# schem.net
KiCad netlist of a schematic drawn in EAGLE
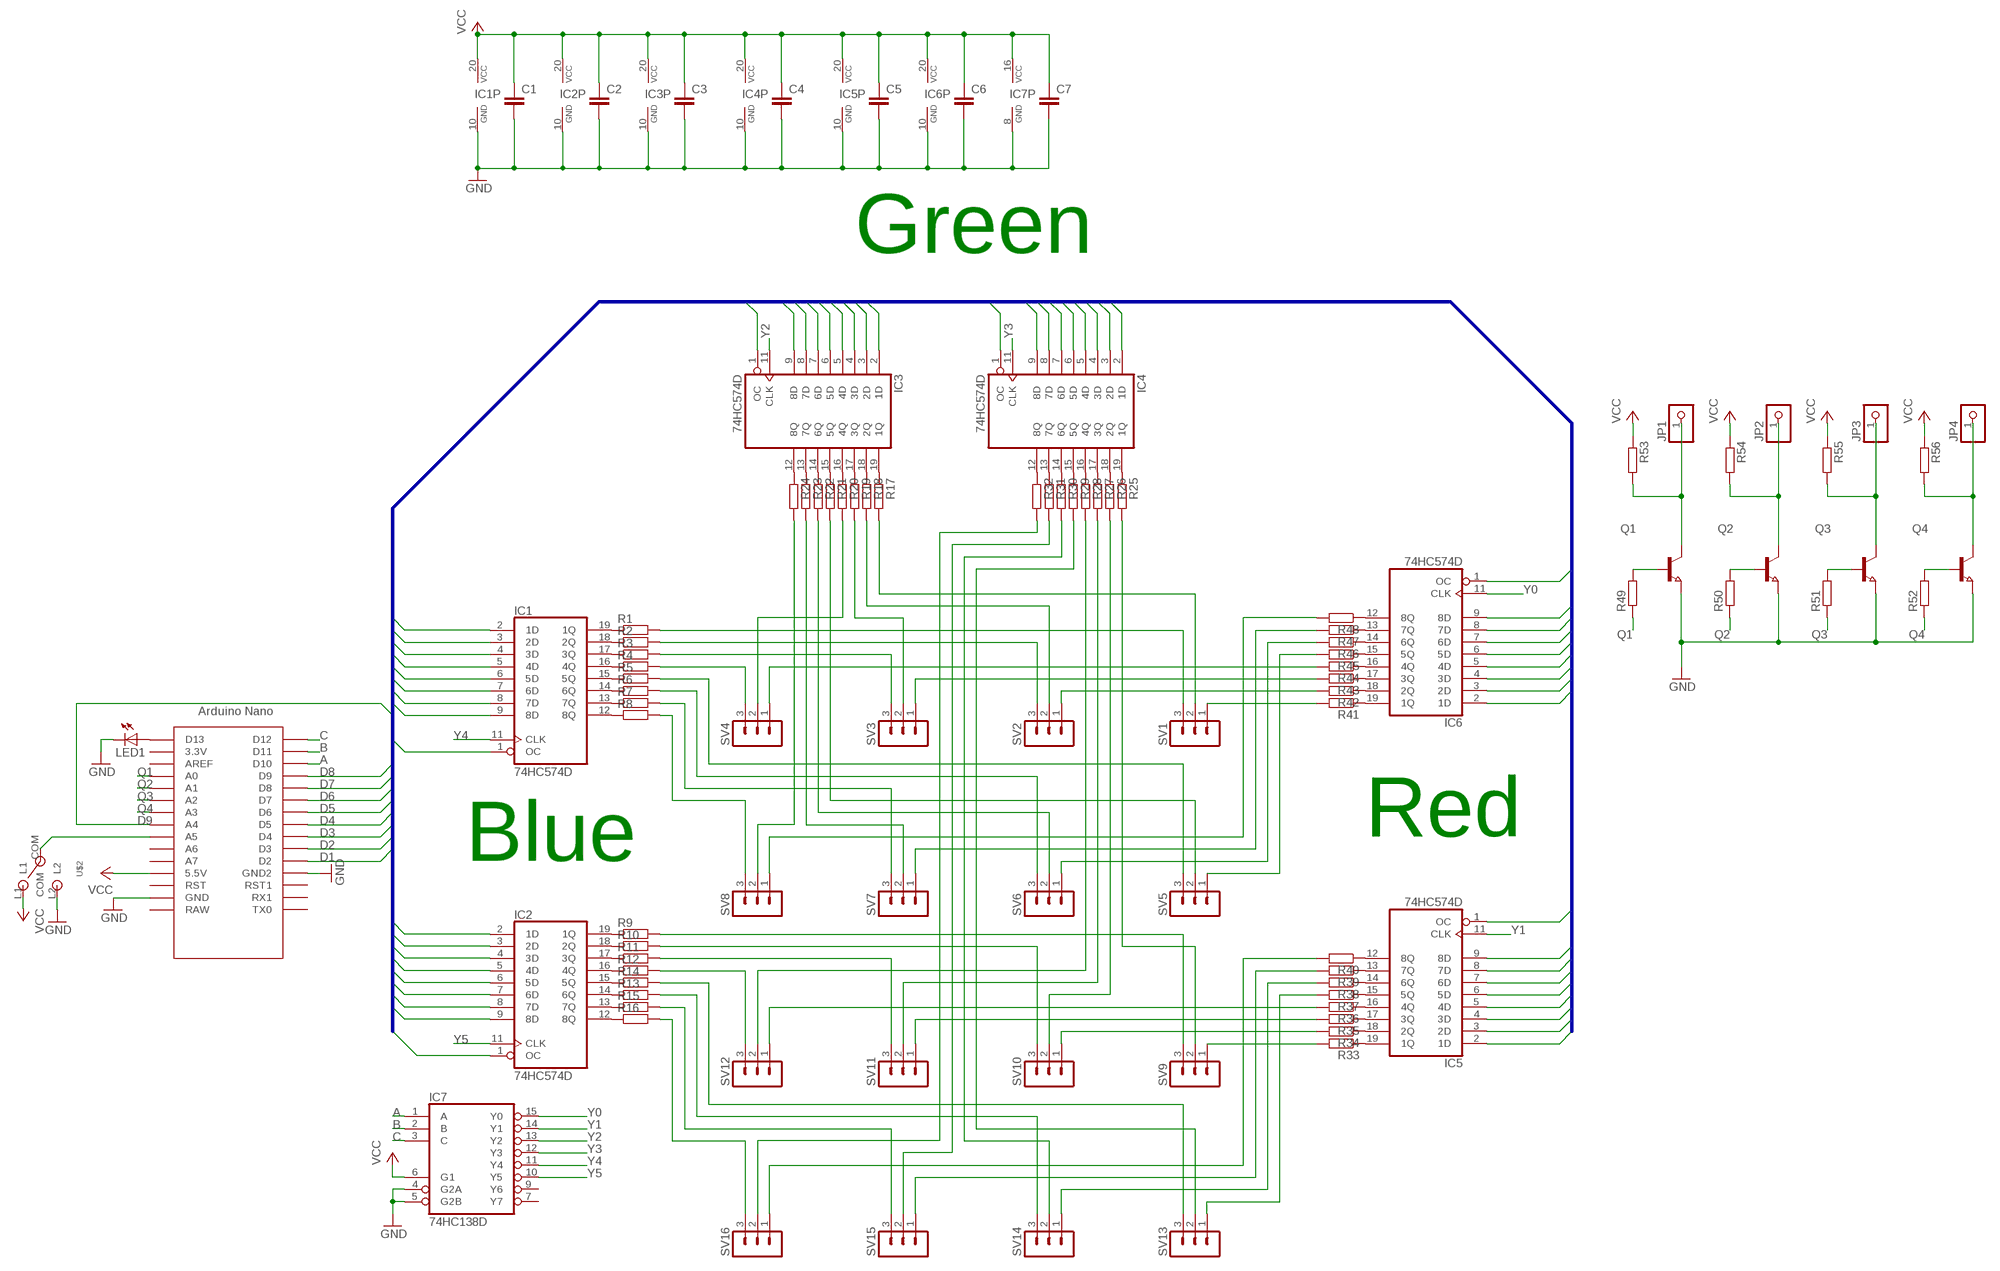
[diagram p0: schematic, sheet 1]

(export (version "E")
  (design (tool "Eeschema 10.0.6"))
  (components
    (comp (ref "C1")
      (value "C-EUC0805")
      (footprint "eagle-import:C0805")
      (libsource (lib "eagle-import") (part "C-EUC0805"))
    )
    (comp (ref "C2")
      (value "C-EUC0805")
      (footprint "eagle-import:C0805")
      (libsource (lib "eagle-import") (part "C-EUC0805"))
    )
    (comp (ref "C3")
      (value "C-EUC0805")
      (footprint "eagle-import:C0805")
      (libsource (lib "eagle-import") (part "C-EUC0805"))
    )
    (comp (ref "C4")
      (value "C-EUC0805")
      (footprint "eagle-import:C0805")
      (libsource (lib "eagle-import") (part "C-EUC0805"))
    )
    (comp (ref "C5")
      (value "C-EUC0805")
      (footprint "eagle-import:C0805")
      (libsource (lib "eagle-import") (part "C-EUC0805"))
    )
    (comp (ref "C6")
      (value "C-EUC0805")
      (footprint "eagle-import:C0805")
      (libsource (lib "eagle-import") (part "C-EUC0805"))
    )
    (comp (ref "C7")
      (value "C-EUC0805")
      (footprint "eagle-import:C0805")
      (libsource (lib "eagle-import") (part "C-EUC0805"))
    )
    (comp (ref "IC1")
      (value "74HC574D")
      (footprint "eagle-import:SO20W")
      (libsource (lib "eagle-import") (part "74574DHC"))
    )
    (comp (ref "IC2")
      (value "74HC574D")
      (footprint "eagle-import:SO20W")
      (libsource (lib "eagle-import") (part "74574DHC"))
    )
    (comp (ref "IC3")
      (value "74HC574D")
      (footprint "eagle-import:SO20W")
      (libsource (lib "eagle-import") (part "74574DHC"))
    )
    (comp (ref "IC4")
      (value "74HC574D")
      (footprint "eagle-import:SO20W")
      (libsource (lib "eagle-import") (part "74574DHC"))
    )
    (comp (ref "IC5")
      (value "74HC574D")
      (footprint "eagle-import:SO20W")
      (libsource (lib "eagle-import") (part "74574DHC"))
    )
    (comp (ref "IC6")
      (value "74HC574D")
      (footprint "eagle-import:SO20W")
      (libsource (lib "eagle-import") (part "74574DHC"))
    )
    (comp (ref "IC7")
      (value "74HC138D")
      (footprint "eagle-import:SO16")
      (libsource (lib "eagle-import") (part "74138DHC"))
    )
    (comp (ref "JP1")
      (value "PINHD-1X1")
      (footprint "eagle-import:1X01")
      (libsource (lib "eagle-import") (part "PINHD-1X1"))
    )
    (comp (ref "JP2")
      (value "PINHD-1X1")
      (footprint "eagle-import:1X01")
      (libsource (lib "eagle-import") (part "PINHD-1X1"))
    )
    (comp (ref "JP3")
      (value "PINHD-1X1")
      (footprint "eagle-import:1X01")
      (libsource (lib "eagle-import") (part "PINHD-1X1"))
    )
    (comp (ref "JP4")
      (value "PINHD-1X1")
      (footprint "eagle-import:1X01")
      (libsource (lib "eagle-import") (part "PINHD-1X1"))
    )
    (comp (ref "LED1")
      (value "LEDCHIP-LED0805")
      (footprint "eagle-import:CHIP-LED0805")
      (libsource (lib "eagle-import") (part "LEDCHIP-LED0805"))
    )
    (comp (ref "Q1")
      (value "NPN-TRANSISTOR_SOT23")
      (footprint "eagle-import:SOT23")
      (libsource (lib "eagle-import") (part "NPN-TRANSISTOR_SOT23"))
    )
    (comp (ref "Q2")
      (value "NPN-TRANSISTOR_SOT23")
      (footprint "eagle-import:SOT23")
      (libsource (lib "eagle-import") (part "NPN-TRANSISTOR_SOT23"))
    )
    (comp (ref "Q3")
      (value "NPN-TRANSISTOR_SOT23")
      (footprint "eagle-import:SOT23")
      (libsource (lib "eagle-import") (part "NPN-TRANSISTOR_SOT23"))
    )
    (comp (ref "Q4")
      (value "NPN-TRANSISTOR_SOT23")
      (footprint "eagle-import:SOT23")
      (libsource (lib "eagle-import") (part "NPN-TRANSISTOR_SOT23"))
    )
    (comp (ref "R1")
      (value "R-EU_R0805")
      (footprint "eagle-import:R0805")
      (libsource (lib "eagle-import") (part "R-EU_R0805"))
    )
    (comp (ref "R2")
      (value "R-EU_R0805")
      (footprint "eagle-import:R0805")
      (libsource (lib "eagle-import") (part "R-EU_R0805"))
    )
    (comp (ref "R3")
      (value "R-EU_R0805")
      (footprint "eagle-import:R0805")
      (libsource (lib "eagle-import") (part "R-EU_R0805"))
    )
    (comp (ref "R4")
      (value "R-EU_R0805")
      (footprint "eagle-import:R0805")
      (libsource (lib "eagle-import") (part "R-EU_R0805"))
    )
    (comp (ref "R5")
      (value "R-EU_R0805")
      (footprint "eagle-import:R0805")
      (libsource (lib "eagle-import") (part "R-EU_R0805"))
    )
    (comp (ref "R6")
      (value "R-EU_R0805")
      (footprint "eagle-import:R0805")
      (libsource (lib "eagle-import") (part "R-EU_R0805"))
    )
    (comp (ref "R7")
      (value "R-EU_R0805")
      (footprint "eagle-import:R0805")
      (libsource (lib "eagle-import") (part "R-EU_R0805"))
    )
    (comp (ref "R8")
      (value "R-EU_R0805")
      (footprint "eagle-import:R0805")
      (libsource (lib "eagle-import") (part "R-EU_R0805"))
    )
    (comp (ref "R9")
      (value "R-EU_R0805")
      (footprint "eagle-import:R0805")
      (libsource (lib "eagle-import") (part "R-EU_R0805"))
    )
    (comp (ref "R10")
      (value "R-EU_R0805")
      (footprint "eagle-import:R0805")
      (libsource (lib "eagle-import") (part "R-EU_R0805"))
    )
    (comp (ref "R11")
      (value "R-EU_R0805")
      (footprint "eagle-import:R0805")
      (libsource (lib "eagle-import") (part "R-EU_R0805"))
    )
    (comp (ref "R12")
      (value "R-EU_R0805")
      (footprint "eagle-import:R0805")
      (libsource (lib "eagle-import") (part "R-EU_R0805"))
    )
    (comp (ref "R13")
      (value "R-EU_R0805")
      (footprint "eagle-import:R0805")
      (libsource (lib "eagle-import") (part "R-EU_R0805"))
    )
    (comp (ref "R14")
      (value "R-EU_R0805")
      (footprint "eagle-import:R0805")
      (libsource (lib "eagle-import") (part "R-EU_R0805"))
    )
    (comp (ref "R15")
      (value "R-EU_R0805")
      (footprint "eagle-import:R0805")
      (libsource (lib "eagle-import") (part "R-EU_R0805"))
    )
    (comp (ref "R16")
      (value "R-EU_R0805")
      (footprint "eagle-import:R0805")
      (libsource (lib "eagle-import") (part "R-EU_R0805"))
    )
    (comp (ref "R17")
      (value "R-EU_R0805")
      (footprint "eagle-import:R0805")
      (libsource (lib "eagle-import") (part "R-EU_R0805"))
    )
    (comp (ref "R18")
      (value "R-EU_R0805")
      (footprint "eagle-import:R0805")
      (libsource (lib "eagle-import") (part "R-EU_R0805"))
    )
    (comp (ref "R19")
      (value "R-EU_R0805")
      (footprint "eagle-import:R0805")
      (libsource (lib "eagle-import") (part "R-EU_R0805"))
    )
    (comp (ref "R20")
      (value "R-EU_R0805")
      (footprint "eagle-import:R0805")
      (libsource (lib "eagle-import") (part "R-EU_R0805"))
    )
    (comp (ref "R21")
      (value "R-EU_R0805")
      (footprint "eagle-import:R0805")
      (libsource (lib "eagle-import") (part "R-EU_R0805"))
    )
    (comp (ref "R22")
      (value "R-EU_R0805")
      (footprint "eagle-import:R0805")
      (libsource (lib "eagle-import") (part "R-EU_R0805"))
    )
    (comp (ref "R23")
      (value "R-EU_R0805")
      (footprint "eagle-import:R0805")
      (libsource (lib "eagle-import") (part "R-EU_R0805"))
    )
    (comp (ref "R24")
      (value "R-EU_R0805")
      (footprint "eagle-import:R0805")
      (libsource (lib "eagle-import") (part "R-EU_R0805"))
    )
    (comp (ref "R25")
      (value "R-EU_R0805")
      (footprint "eagle-import:R0805")
      (libsource (lib "eagle-import") (part "R-EU_R0805"))
    )
    (comp (ref "R26")
      (value "R-EU_R0805")
      (footprint "eagle-import:R0805")
      (libsource (lib "eagle-import") (part "R-EU_R0805"))
    )
    (comp (ref "R27")
      (value "R-EU_R0805")
      (footprint "eagle-import:R0805")
      (libsource (lib "eagle-import") (part "R-EU_R0805"))
    )
    (comp (ref "R28")
      (value "R-EU_R0805")
      (footprint "eagle-import:R0805")
      (libsource (lib "eagle-import") (part "R-EU_R0805"))
    )
    (comp (ref "R29")
      (value "R-EU_R0805")
      (footprint "eagle-import:R0805")
      (libsource (lib "eagle-import") (part "R-EU_R0805"))
    )
    (comp (ref "R30")
      (value "R-EU_R0805")
      (footprint "eagle-import:R0805")
      (libsource (lib "eagle-import") (part "R-EU_R0805"))
    )
    (comp (ref "R31")
      (value "R-EU_R0805")
      (footprint "eagle-import:R0805")
      (libsource (lib "eagle-import") (part "R-EU_R0805"))
    )
    (comp (ref "R32")
      (value "R-EU_R0805")
      (footprint "eagle-import:R0805")
      (libsource (lib "eagle-import") (part "R-EU_R0805"))
    )
    (comp (ref "R33")
      (value "R-EU_R0805")
      (footprint "eagle-import:R0805")
      (libsource (lib "eagle-import") (part "R-EU_R0805"))
    )
    (comp (ref "R34")
      (value "R-EU_R0805")
      (footprint "eagle-import:R0805")
      (libsource (lib "eagle-import") (part "R-EU_R0805"))
    )
    (comp (ref "R35")
      (value "R-EU_R0805")
      (footprint "eagle-import:R0805")
      (libsource (lib "eagle-import") (part "R-EU_R0805"))
    )
    (comp (ref "R36")
      (value "R-EU_R0805")
      (footprint "eagle-import:R0805")
      (libsource (lib "eagle-import") (part "R-EU_R0805"))
    )
    (comp (ref "R37")
      (value "R-EU_R0805")
      (footprint "eagle-import:R0805")
      (libsource (lib "eagle-import") (part "R-EU_R0805"))
    )
    (comp (ref "R38")
      (value "R-EU_R0805")
      (footprint "eagle-import:R0805")
      (libsource (lib "eagle-import") (part "R-EU_R0805"))
    )
    (comp (ref "R39")
      (value "R-EU_R0805")
      (footprint "eagle-import:R0805")
      (libsource (lib "eagle-import") (part "R-EU_R0805"))
    )
    (comp (ref "R40")
      (value "R-EU_R0805")
      (footprint "eagle-import:R0805")
      (libsource (lib "eagle-import") (part "R-EU_R0805"))
    )
    (comp (ref "R41")
      (value "R-EU_R0805")
      (footprint "eagle-import:R0805")
      (libsource (lib "eagle-import") (part "R-EU_R0805"))
    )
    (comp (ref "R42")
      (value "R-EU_R0805")
      (footprint "eagle-import:R0805")
      (libsource (lib "eagle-import") (part "R-EU_R0805"))
    )
    (comp (ref "R43")
      (value "R-EU_R0805")
      (footprint "eagle-import:R0805")
      (libsource (lib "eagle-import") (part "R-EU_R0805"))
    )
    (comp (ref "R44")
      (value "R-EU_R0805")
      (footprint "eagle-import:R0805")
      (libsource (lib "eagle-import") (part "R-EU_R0805"))
    )
    (comp (ref "R45")
      (value "R-EU_R0805")
      (footprint "eagle-import:R0805")
      (libsource (lib "eagle-import") (part "R-EU_R0805"))
    )
    (comp (ref "R46")
      (value "R-EU_R0805")
      (footprint "eagle-import:R0805")
      (libsource (lib "eagle-import") (part "R-EU_R0805"))
    )
    (comp (ref "R47")
      (value "R-EU_R0805")
      (footprint "eagle-import:R0805")
      (libsource (lib "eagle-import") (part "R-EU_R0805"))
    )
    (comp (ref "R48")
      (value "R-EU_R0805")
      (footprint "eagle-import:R0805")
      (libsource (lib "eagle-import") (part "R-EU_R0805"))
    )
    (comp (ref "R49")
      (value "R-EU_R0805")
      (footprint "eagle-import:R0805")
      (libsource (lib "eagle-import") (part "R-EU_R0805"))
    )
    (comp (ref "R50")
      (value "R-EU_R0805")
      (footprint "eagle-import:R0805")
      (libsource (lib "eagle-import") (part "R-EU_R0805"))
    )
    (comp (ref "R51")
      (value "R-EU_R0805")
      (footprint "eagle-import:R0805")
      (libsource (lib "eagle-import") (part "R-EU_R0805"))
    )
    (comp (ref "R52")
      (value "R-EU_R0805")
      (footprint "eagle-import:R0805")
      (libsource (lib "eagle-import") (part "R-EU_R0805"))
    )
    (comp (ref "R53")
      (value "R-EU_R0805")
      (footprint "eagle-import:R0805")
      (libsource (lib "eagle-import") (part "R-EU_R0805"))
    )
    (comp (ref "R54")
      (value "R-EU_R0805")
      (footprint "eagle-import:R0805")
      (libsource (lib "eagle-import") (part "R-EU_R0805"))
    )
    (comp (ref "R55")
      (value "R-EU_R0805")
      (footprint "eagle-import:R0805")
      (libsource (lib "eagle-import") (part "R-EU_R0805"))
    )
    (comp (ref "R56")
      (value "R-EU_R0805")
      (footprint "eagle-import:R0805")
      (libsource (lib "eagle-import") (part "R-EU_R0805"))
    )
    (comp (ref "SV1")
      (value "MA03-1")
      (footprint "eagle-import:MA03-1")
      (libsource (lib "eagle-import") (part "MA03-1"))
    )
    (comp (ref "SV2")
      (value "MA03-1")
      (footprint "eagle-import:MA03-1")
      (libsource (lib "eagle-import") (part "MA03-1"))
    )
    (comp (ref "SV3")
      (value "MA03-1")
      (footprint "eagle-import:MA03-1")
      (libsource (lib "eagle-import") (part "MA03-1"))
    )
    (comp (ref "SV4")
      (value "MA03-1")
      (footprint "eagle-import:MA03-1")
      (libsource (lib "eagle-import") (part "MA03-1"))
    )
    (comp (ref "SV5")
      (value "MA03-1")
      (footprint "eagle-import:MA03-1")
      (libsource (lib "eagle-import") (part "MA03-1"))
    )
    (comp (ref "SV6")
      (value "MA03-1")
      (footprint "eagle-import:MA03-1")
      (libsource (lib "eagle-import") (part "MA03-1"))
    )
    (comp (ref "SV7")
      (value "MA03-1")
      (footprint "eagle-import:MA03-1")
      (libsource (lib "eagle-import") (part "MA03-1"))
    )
    (comp (ref "SV8")
      (value "MA03-1")
      (footprint "eagle-import:MA03-1")
      (libsource (lib "eagle-import") (part "MA03-1"))
    )
    (comp (ref "SV9")
      (value "MA03-1")
      (footprint "eagle-import:MA03-1")
      (libsource (lib "eagle-import") (part "MA03-1"))
    )
    (comp (ref "SV10")
      (value "MA03-1")
      (footprint "eagle-import:MA03-1")
      (libsource (lib "eagle-import") (part "MA03-1"))
    )
    (comp (ref "SV11")
      (value "MA03-1")
      (footprint "eagle-import:MA03-1")
      (libsource (lib "eagle-import") (part "MA03-1"))
    )
    (comp (ref "SV12")
      (value "MA03-1")
      (footprint "eagle-import:MA03-1")
      (libsource (lib "eagle-import") (part "MA03-1"))
    )
    (comp (ref "SV13")
      (value "MA03-1")
      (footprint "eagle-import:MA03-1")
      (libsource (lib "eagle-import") (part "MA03-1"))
    )
    (comp (ref "SV14")
      (value "MA03-1")
      (footprint "eagle-import:MA03-1")
      (libsource (lib "eagle-import") (part "MA03-1"))
    )
    (comp (ref "SV15")
      (value "MA03-1")
      (footprint "eagle-import:MA03-1")
      (libsource (lib "eagle-import") (part "MA03-1"))
    )
    (comp (ref "SV16")
      (value "MA03-1")
      (footprint "eagle-import:MA03-1")
      (libsource (lib "eagle-import") (part "MA03-1"))
    )
    (comp (ref "U$1")
      (value "NANO")
      (footprint "eagle-import:NANO")
      (libsource (lib "eagle-import") (part "NANO"))
    )
    (comp (ref "U$2")
      (value "MSK-12C02_SMD_SPDT_SWITCH")
      (footprint "eagle-import:MSK-12C02")
      (libsource (lib "eagle-import") (part "MSK-12C02_SMD_SPDT_SWITCH"))
    )
  )
  (nets
    (net (code "1") (name "/A") (class "Default")
      (node (ref "IC7") (pin "1") (pinfunction "A_1") (pintype "input"))
      (node (ref "U$1") (pin "D10") (pinfunction "D10_D10") (pintype "bidirectional"))
    )
    (net (code "2") (name "/B") (class "Default")
      (node (ref "IC7") (pin "2") (pinfunction "B_2") (pintype "input"))
      (node (ref "U$1") (pin "D11") (pinfunction "D11_D11") (pintype "bidirectional"))
    )
    (net (code "3") (name "/C") (class "Default")
      (node (ref "IC7") (pin "3") (pinfunction "C_3") (pintype "input"))
      (node (ref "U$1") (pin "D12") (pinfunction "D12_D12") (pintype "bidirectional"))
    )
    (net (code "4") (name "/D1") (class "Default")
      (node (ref "IC1") (pin "2") (pinfunction "1D_2") (pintype "input"))
      (node (ref "IC2") (pin "2") (pinfunction "1D_2") (pintype "input"))
      (node (ref "IC3") (pin "2") (pinfunction "1D_2") (pintype "input"))
      (node (ref "IC4") (pin "2") (pinfunction "1D_2") (pintype "input"))
      (node (ref "IC5") (pin "2") (pinfunction "1D_2") (pintype "input"))
      (node (ref "IC6") (pin "2") (pinfunction "1D_2") (pintype "input"))
      (node (ref "U$1") (pin "D2") (pinfunction "D2_D2") (pintype "bidirectional"))
    )
    (net (code "5") (name "/D2") (class "Default")
      (node (ref "IC1") (pin "3") (pinfunction "2D_3") (pintype "input"))
      (node (ref "IC2") (pin "3") (pinfunction "2D_3") (pintype "input"))
      (node (ref "IC3") (pin "3") (pinfunction "2D_3") (pintype "input"))
      (node (ref "IC4") (pin "3") (pinfunction "2D_3") (pintype "input"))
      (node (ref "IC5") (pin "3") (pinfunction "2D_3") (pintype "input"))
      (node (ref "IC6") (pin "3") (pinfunction "2D_3") (pintype "input"))
      (node (ref "U$1") (pin "D3") (pinfunction "D3_D3") (pintype "bidirectional"))
    )
    (net (code "6") (name "/D3") (class "Default")
      (node (ref "IC1") (pin "4") (pinfunction "3D_4") (pintype "input"))
      (node (ref "IC2") (pin "4") (pinfunction "3D_4") (pintype "input"))
      (node (ref "IC3") (pin "4") (pinfunction "3D_4") (pintype "input"))
      (node (ref "IC4") (pin "4") (pinfunction "3D_4") (pintype "input"))
      (node (ref "IC5") (pin "4") (pinfunction "3D_4") (pintype "input"))
      (node (ref "IC6") (pin "4") (pinfunction "3D_4") (pintype "input"))
      (node (ref "U$1") (pin "D4") (pinfunction "D4_D4") (pintype "bidirectional"))
    )
    (net (code "7") (name "/D4") (class "Default")
      (node (ref "IC1") (pin "5") (pinfunction "4D_5") (pintype "input"))
      (node (ref "IC2") (pin "5") (pinfunction "4D_5") (pintype "input"))
      (node (ref "IC3") (pin "5") (pinfunction "4D_5") (pintype "input"))
      (node (ref "IC4") (pin "5") (pinfunction "4D_5") (pintype "input"))
      (node (ref "IC5") (pin "5") (pinfunction "4D_5") (pintype "input"))
      (node (ref "IC6") (pin "5") (pinfunction "4D_5") (pintype "input"))
      (node (ref "U$1") (pin "D5") (pinfunction "D5_D5") (pintype "bidirectional"))
    )
    (net (code "8") (name "/D5") (class "Default")
      (node (ref "IC1") (pin "6") (pinfunction "5D_6") (pintype "input"))
      (node (ref "IC2") (pin "6") (pinfunction "5D_6") (pintype "input"))
      (node (ref "IC3") (pin "6") (pinfunction "5D_6") (pintype "input"))
      (node (ref "IC4") (pin "6") (pinfunction "5D_6") (pintype "input"))
      (node (ref "IC5") (pin "6") (pinfunction "5D_6") (pintype "input"))
      (node (ref "IC6") (pin "6") (pinfunction "5D_6") (pintype "input"))
      (node (ref "U$1") (pin "D6") (pinfunction "D6_D6") (pintype "bidirectional"))
    )
    (net (code "9") (name "/D6") (class "Default")
      (node (ref "IC1") (pin "7") (pinfunction "6D_7") (pintype "input"))
      (node (ref "IC2") (pin "7") (pinfunction "6D_7") (pintype "input"))
      (node (ref "IC3") (pin "7") (pinfunction "6D_7") (pintype "input"))
      (node (ref "IC4") (pin "7") (pinfunction "6D_7") (pintype "input"))
      (node (ref "IC5") (pin "7") (pinfunction "6D_7") (pintype "input"))
      (node (ref "IC6") (pin "7") (pinfunction "6D_7") (pintype "input"))
      (node (ref "U$1") (pin "D7") (pinfunction "D7_D7") (pintype "bidirectional"))
    )
    (net (code "10") (name "/D7") (class "Default")
      (node (ref "IC1") (pin "8") (pinfunction "7D_8") (pintype "input"))
      (node (ref "IC2") (pin "8") (pinfunction "7D_8") (pintype "input"))
      (node (ref "IC3") (pin "8") (pinfunction "7D_8") (pintype "input"))
      (node (ref "IC4") (pin "8") (pinfunction "7D_8") (pintype "input"))
      (node (ref "IC5") (pin "8") (pinfunction "7D_8") (pintype "input"))
      (node (ref "IC6") (pin "8") (pinfunction "7D_8") (pintype "input"))
      (node (ref "U$1") (pin "D8") (pinfunction "D8_D8") (pintype "bidirectional"))
    )
    (net (code "11") (name "/D8") (class "Default")
      (node (ref "IC1") (pin "9") (pinfunction "8D_9") (pintype "input"))
      (node (ref "IC2") (pin "9") (pinfunction "8D_9") (pintype "input"))
      (node (ref "IC3") (pin "9") (pinfunction "8D_9") (pintype "input"))
      (node (ref "IC4") (pin "9") (pinfunction "8D_9") (pintype "input"))
      (node (ref "IC5") (pin "9") (pinfunction "8D_9") (pintype "input"))
      (node (ref "IC6") (pin "9") (pinfunction "8D_9") (pintype "input"))
      (node (ref "U$1") (pin "D9") (pinfunction "D9_D9") (pintype "bidirectional"))
    )
    (net (code "12") (name "/D9") (class "Default")
      (node (ref "IC1") (pin "1") (pinfunction "OC_1") (pintype "input"))
      (node (ref "IC2") (pin "1") (pinfunction "OC_1") (pintype "input"))
      (node (ref "IC3") (pin "1") (pinfunction "OC_1") (pintype "input"))
      (node (ref "IC4") (pin "1") (pinfunction "OC_1") (pintype "input"))
      (node (ref "IC5") (pin "1") (pinfunction "OC_1") (pintype "input"))
      (node (ref "IC6") (pin "1") (pinfunction "OC_1") (pintype "input"))
      (node (ref "U$1") (pin "A4") (pinfunction "A4_A4") (pintype "bidirectional"))
    )
    (net (code "13") (name "/Q1") (class "Default")
      (node (ref "R49") (pin "1") (pinfunction "1_1") (pintype "passive"))
      (node (ref "U$1") (pin "A0") (pinfunction "A0_A0") (pintype "bidirectional"))
    )
    (net (code "14") (name "/Q2") (class "Default")
      (node (ref "R50") (pin "1") (pinfunction "1_1") (pintype "passive"))
      (node (ref "U$1") (pin "A1") (pinfunction "A1_A1") (pintype "bidirectional"))
    )
    (net (code "15") (name "/Q3") (class "Default")
      (node (ref "R51") (pin "1") (pinfunction "1_1") (pintype "passive"))
      (node (ref "U$1") (pin "A2") (pinfunction "A2_A2") (pintype "bidirectional"))
    )
    (net (code "16") (name "/Q4") (class "Default")
      (node (ref "R52") (pin "1") (pinfunction "1_1") (pintype "passive"))
      (node (ref "U$1") (pin "A3") (pinfunction "A3_A3") (pintype "bidirectional"))
    )
    (net (code "17") (name "/Y0") (class "Default")
      (node (ref "IC6") (pin "11") (pinfunction "CLK_11") (pintype "input"))
      (node (ref "IC7") (pin "15") (pinfunction "Y0_15") (pintype "output"))
    )
    (net (code "18") (name "/Y1") (class "Default")
      (node (ref "IC5") (pin "11") (pinfunction "CLK_11") (pintype "input"))
      (node (ref "IC7") (pin "14") (pinfunction "Y1_14") (pintype "output"))
    )
    (net (code "19") (name "/Y2") (class "Default")
      (node (ref "IC3") (pin "11") (pinfunction "CLK_11") (pintype "input"))
      (node (ref "IC7") (pin "13") (pinfunction "Y2_13") (pintype "output"))
    )
    (net (code "20") (name "/Y3") (class "Default")
      (node (ref "IC4") (pin "11") (pinfunction "CLK_11") (pintype "input"))
      (node (ref "IC7") (pin "12") (pinfunction "Y3_12") (pintype "output"))
    )
    (net (code "21") (name "/Y4") (class "Default")
      (node (ref "IC1") (pin "11") (pinfunction "CLK_11") (pintype "input"))
      (node (ref "IC7") (pin "11") (pinfunction "Y4_11") (pintype "output"))
    )
    (net (code "22") (name "/Y5") (class "Default")
      (node (ref "IC2") (pin "11") (pinfunction "CLK_11") (pintype "input"))
      (node (ref "IC7") (pin "10") (pinfunction "Y5_10") (pintype "output"))
    )
    (net (code "23") (name "GND") (class "Default")
      (node (ref "C1") (pin "2") (pinfunction "2_2") (pintype "passive"))
      (node (ref "C2") (pin "2") (pinfunction "2_2") (pintype "passive"))
      (node (ref "C3") (pin "2") (pinfunction "2_2") (pintype "passive"))
      (node (ref "C4") (pin "2") (pinfunction "2_2") (pintype "passive"))
      (node (ref "C5") (pin "2") (pinfunction "2_2") (pintype "passive"))
      (node (ref "C6") (pin "2") (pinfunction "2_2") (pintype "passive"))
      (node (ref "C7") (pin "2") (pinfunction "2_2") (pintype "passive"))
      (node (ref "IC1") (pin "10") (pinfunction "GND_10") (pintype "power_in"))
      (node (ref "IC2") (pin "10") (pinfunction "GND_10") (pintype "power_in"))
      (node (ref "IC3") (pin "10") (pinfunction "GND_10") (pintype "power_in"))
      (node (ref "IC4") (pin "10") (pinfunction "GND_10") (pintype "power_in"))
      (node (ref "IC5") (pin "10") (pinfunction "GND_10") (pintype "power_in"))
      (node (ref "IC6") (pin "10") (pinfunction "GND_10") (pintype "power_in"))
      (node (ref "IC7") (pin "4") (pinfunction "G2A_4") (pintype "input"))
      (node (ref "IC7") (pin "5") (pinfunction "G2B_5") (pintype "input"))
      (node (ref "IC7") (pin "8") (pinfunction "GND_8") (pintype "power_in"))
      (node (ref "LED1") (pin "C") (pinfunction "C_C") (pintype "passive"))
      (node (ref "Q1") (pin "2") (pinfunction "E_2") (pintype "passive"))
      (node (ref "Q2") (pin "2") (pinfunction "E_2") (pintype "passive"))
      (node (ref "Q3") (pin "2") (pinfunction "E_2") (pintype "passive"))
      (node (ref "Q4") (pin "2") (pinfunction "E_2") (pintype "passive"))
      (node (ref "U$1") (pin "GND") (pinfunction "GND_GND") (pintype "bidirectional"))
      (node (ref "U$1") (pin "GND1") (pinfunction "GND2_GND1") (pintype "bidirectional"))
      (node (ref "U$2") (pin "L2") (pinfunction "L2_L2") (pintype "bidirectional"))
    )
    (net (code "24") (name "Net-(IC1A-1Q)") (class "Default")
      (node (ref "IC1") (pin "19") (pinfunction "1Q_19") (pintype "tri_state"))
      (node (ref "R1") (pin "1") (pinfunction "1_1") (pintype "passive"))
    )
    (net (code "25") (name "Net-(IC1A-2Q)") (class "Default")
      (node (ref "IC1") (pin "18") (pinfunction "2Q_18") (pintype "tri_state"))
      (node (ref "R2") (pin "1") (pinfunction "1_1") (pintype "passive"))
    )
    (net (code "26") (name "Net-(IC1A-3Q)") (class "Default")
      (node (ref "IC1") (pin "17") (pinfunction "3Q_17") (pintype "tri_state"))
      (node (ref "R3") (pin "1") (pinfunction "1_1") (pintype "passive"))
    )
    (net (code "27") (name "Net-(IC1A-4Q)") (class "Default")
      (node (ref "IC1") (pin "16") (pinfunction "4Q_16") (pintype "tri_state"))
      (node (ref "R4") (pin "1") (pinfunction "1_1") (pintype "passive"))
    )
    (net (code "28") (name "Net-(IC1A-5Q)") (class "Default")
      (node (ref "IC1") (pin "15") (pinfunction "5Q_15") (pintype "tri_state"))
      (node (ref "R5") (pin "1") (pinfunction "1_1") (pintype "passive"))
    )
    (net (code "29") (name "Net-(IC1A-6Q)") (class "Default")
      (node (ref "IC1") (pin "14") (pinfunction "6Q_14") (pintype "tri_state"))
      (node (ref "R6") (pin "1") (pinfunction "1_1") (pintype "passive"))
    )
    (net (code "30") (name "Net-(IC1A-7Q)") (class "Default")
      (node (ref "IC1") (pin "13") (pinfunction "7Q_13") (pintype "tri_state"))
      (node (ref "R7") (pin "1") (pinfunction "1_1") (pintype "passive"))
    )
    (net (code "31") (name "Net-(IC1A-8Q)") (class "Default")
      (node (ref "IC1") (pin "12") (pinfunction "8Q_12") (pintype "tri_state"))
      (node (ref "R8") (pin "1") (pinfunction "1_1") (pintype "passive"))
    )
    (net (code "32") (name "Net-(IC2A-1Q)") (class "Default")
      (node (ref "IC2") (pin "19") (pinfunction "1Q_19") (pintype "tri_state"))
      (node (ref "R9") (pin "1") (pinfunction "1_1") (pintype "passive"))
    )
    (net (code "33") (name "Net-(IC2A-2Q)") (class "Default")
      (node (ref "IC2") (pin "18") (pinfunction "2Q_18") (pintype "tri_state"))
      (node (ref "R10") (pin "1") (pinfunction "1_1") (pintype "passive"))
    )
    (net (code "34") (name "Net-(IC2A-3Q)") (class "Default")
      (node (ref "IC2") (pin "17") (pinfunction "3Q_17") (pintype "tri_state"))
      (node (ref "R11") (pin "1") (pinfunction "1_1") (pintype "passive"))
    )
    (net (code "35") (name "Net-(IC2A-4Q)") (class "Default")
      (node (ref "IC2") (pin "16") (pinfunction "4Q_16") (pintype "tri_state"))
      (node (ref "R12") (pin "1") (pinfunction "1_1") (pintype "passive"))
    )
    (net (code "36") (name "Net-(IC2A-5Q)") (class "Default")
      (node (ref "IC2") (pin "15") (pinfunction "5Q_15") (pintype "tri_state"))
      (node (ref "R14") (pin "1") (pinfunction "1_1") (pintype "passive"))
    )
    (net (code "37") (name "Net-(IC2A-6Q)") (class "Default")
      (node (ref "IC2") (pin "14") (pinfunction "6Q_14") (pintype "tri_state"))
      (node (ref "R13") (pin "1") (pinfunction "1_1") (pintype "passive"))
    )
    (net (code "38") (name "Net-(IC2A-7Q)") (class "Default")
      (node (ref "IC2") (pin "13") (pinfunction "7Q_13") (pintype "tri_state"))
      (node (ref "R15") (pin "1") (pinfunction "1_1") (pintype "passive"))
    )
    (net (code "39") (name "Net-(IC2A-8Q)") (class "Default")
      (node (ref "IC2") (pin "12") (pinfunction "8Q_12") (pintype "tri_state"))
      (node (ref "R16") (pin "1") (pinfunction "1_1") (pintype "passive"))
    )
    (net (code "40") (name "Net-(IC3A-1Q)") (class "Default")
      (node (ref "IC3") (pin "19") (pinfunction "1Q_19") (pintype "tri_state"))
      (node (ref "R17") (pin "1") (pinfunction "1_1") (pintype "passive"))
    )
    (net (code "41") (name "Net-(IC3A-2Q)") (class "Default")
      (node (ref "IC3") (pin "18") (pinfunction "2Q_18") (pintype "tri_state"))
      (node (ref "R18") (pin "1") (pinfunction "1_1") (pintype "passive"))
    )
    (net (code "42") (name "Net-(IC3A-3Q)") (class "Default")
      (node (ref "IC3") (pin "17") (pinfunction "3Q_17") (pintype "tri_state"))
      (node (ref "R19") (pin "1") (pinfunction "1_1") (pintype "passive"))
    )
    (net (code "43") (name "Net-(IC3A-4Q)") (class "Default")
      (node (ref "IC3") (pin "16") (pinfunction "4Q_16") (pintype "tri_state"))
      (node (ref "R20") (pin "1") (pinfunction "1_1") (pintype "passive"))
    )
    (net (code "44") (name "Net-(IC3A-5Q)") (class "Default")
      (node (ref "IC3") (pin "15") (pinfunction "5Q_15") (pintype "tri_state"))
      (node (ref "R21") (pin "1") (pinfunction "1_1") (pintype "passive"))
    )
    (net (code "45") (name "Net-(IC3A-6Q)") (class "Default")
      (node (ref "IC3") (pin "14") (pinfunction "6Q_14") (pintype "tri_state"))
      (node (ref "R22") (pin "1") (pinfunction "1_1") (pintype "passive"))
    )
    (net (code "46") (name "Net-(IC3A-7Q)") (class "Default")
      (node (ref "IC3") (pin "13") (pinfunction "7Q_13") (pintype "tri_state"))
      (node (ref "R23") (pin "1") (pinfunction "1_1") (pintype "passive"))
    )
    (net (code "47") (name "Net-(IC3A-8Q)") (class "Default")
      (node (ref "IC3") (pin "12") (pinfunction "8Q_12") (pintype "tri_state"))
      (node (ref "R24") (pin "1") (pinfunction "1_1") (pintype "passive"))
    )
    (net (code "48") (name "Net-(IC4A-1Q)") (class "Default")
      (node (ref "IC4") (pin "19") (pinfunction "1Q_19") (pintype "tri_state"))
      (node (ref "R25") (pin "1") (pinfunction "1_1") (pintype "passive"))
    )
    (net (code "49") (name "Net-(IC4A-2Q)") (class "Default")
      (node (ref "IC4") (pin "18") (pinfunction "2Q_18") (pintype "tri_state"))
      (node (ref "R26") (pin "1") (pinfunction "1_1") (pintype "passive"))
    )
    (net (code "50") (name "Net-(IC4A-3Q)") (class "Default")
      (node (ref "IC4") (pin "17") (pinfunction "3Q_17") (pintype "tri_state"))
      (node (ref "R27") (pin "1") (pinfunction "1_1") (pintype "passive"))
    )
    (net (code "51") (name "Net-(IC4A-4Q)") (class "Default")
      (node (ref "IC4") (pin "16") (pinfunction "4Q_16") (pintype "tri_state"))
      (node (ref "R28") (pin "1") (pinfunction "1_1") (pintype "passive"))
    )
    (net (code "52") (name "Net-(IC4A-5Q)") (class "Default")
      (node (ref "IC4") (pin "15") (pinfunction "5Q_15") (pintype "tri_state"))
      (node (ref "R29") (pin "1") (pinfunction "1_1") (pintype "passive"))
    )
    (net (code "53") (name "Net-(IC4A-6Q)") (class "Default")
      (node (ref "IC4") (pin "14") (pinfunction "6Q_14") (pintype "tri_state"))
      (node (ref "R30") (pin "1") (pinfunction "1_1") (pintype "passive"))
    )
    (net (code "54") (name "Net-(IC4A-7Q)") (class "Default")
      (node (ref "IC4") (pin "13") (pinfunction "7Q_13") (pintype "tri_state"))
      (node (ref "R31") (pin "1") (pinfunction "1_1") (pintype "passive"))
    )
    (net (code "55") (name "Net-(IC4A-8Q)") (class "Default")
      (node (ref "IC4") (pin "12") (pinfunction "8Q_12") (pintype "tri_state"))
      (node (ref "R32") (pin "1") (pinfunction "1_1") (pintype "passive"))
    )
    (net (code "56") (name "Net-(IC5A-1Q)") (class "Default")
      (node (ref "IC5") (pin "19") (pinfunction "1Q_19") (pintype "tri_state"))
      (node (ref "R33") (pin "1") (pinfunction "1_1") (pintype "passive"))
    )
    (net (code "57") (name "Net-(IC5A-2Q)") (class "Default")
      (node (ref "IC5") (pin "18") (pinfunction "2Q_18") (pintype "tri_state"))
      (node (ref "R34") (pin "1") (pinfunction "1_1") (pintype "passive"))
    )
    (net (code "58") (name "Net-(IC5A-3Q)") (class "Default")
      (node (ref "IC5") (pin "17") (pinfunction "3Q_17") (pintype "tri_state"))
      (node (ref "R35") (pin "1") (pinfunction "1_1") (pintype "passive"))
    )
    (net (code "59") (name "Net-(IC5A-4Q)") (class "Default")
      (node (ref "IC5") (pin "16") (pinfunction "4Q_16") (pintype "tri_state"))
      (node (ref "R36") (pin "1") (pinfunction "1_1") (pintype "passive"))
    )
    (net (code "60") (name "Net-(IC5A-5Q)") (class "Default")
      (node (ref "IC5") (pin "15") (pinfunction "5Q_15") (pintype "tri_state"))
      (node (ref "R37") (pin "1") (pinfunction "1_1") (pintype "passive"))
    )
    (net (code "61") (name "Net-(IC5A-6Q)") (class "Default")
      (node (ref "IC5") (pin "14") (pinfunction "6Q_14") (pintype "tri_state"))
      (node (ref "R38") (pin "1") (pinfunction "1_1") (pintype "passive"))
    )
    (net (code "62") (name "Net-(IC5A-7Q)") (class "Default")
      (node (ref "IC5") (pin "13") (pinfunction "7Q_13") (pintype "tri_state"))
      (node (ref "R39") (pin "1") (pinfunction "1_1") (pintype "passive"))
    )
    (net (code "63") (name "Net-(IC5A-8Q)") (class "Default")
      (node (ref "IC5") (pin "12") (pinfunction "8Q_12") (pintype "tri_state"))
      (node (ref "R40") (pin "1") (pinfunction "1_1") (pintype "passive"))
    )
    (net (code "64") (name "Net-(IC6A-1Q)") (class "Default")
      (node (ref "IC6") (pin "19") (pinfunction "1Q_19") (pintype "tri_state"))
      (node (ref "R41") (pin "1") (pinfunction "1_1") (pintype "passive"))
    )
    (net (code "65") (name "Net-(IC6A-2Q)") (class "Default")
      (node (ref "IC6") (pin "18") (pinfunction "2Q_18") (pintype "tri_state"))
      (node (ref "R42") (pin "1") (pinfunction "1_1") (pintype "passive"))
    )
    (net (code "66") (name "Net-(IC6A-3Q)") (class "Default")
      (node (ref "IC6") (pin "17") (pinfunction "3Q_17") (pintype "tri_state"))
      (node (ref "R43") (pin "1") (pinfunction "1_1") (pintype "passive"))
    )
    (net (code "67") (name "Net-(IC6A-4Q)") (class "Default")
      (node (ref "IC6") (pin "16") (pinfunction "4Q_16") (pintype "tri_state"))
      (node (ref "R44") (pin "1") (pinfunction "1_1") (pintype "passive"))
    )
    (net (code "68") (name "Net-(IC6A-5Q)") (class "Default")
      (node (ref "IC6") (pin "15") (pinfunction "5Q_15") (pintype "tri_state"))
      (node (ref "R45") (pin "1") (pinfunction "1_1") (pintype "passive"))
    )
    (net (code "69") (name "Net-(IC6A-6Q)") (class "Default")
      (node (ref "IC6") (pin "14") (pinfunction "6Q_14") (pintype "tri_state"))
      (node (ref "R46") (pin "1") (pinfunction "1_1") (pintype "passive"))
    )
    (net (code "70") (name "Net-(IC6A-7Q)") (class "Default")
      (node (ref "IC6") (pin "13") (pinfunction "7Q_13") (pintype "tri_state"))
      (node (ref "R47") (pin "1") (pinfunction "1_1") (pintype "passive"))
    )
    (net (code "71") (name "Net-(IC6A-8Q)") (class "Default")
      (node (ref "IC6") (pin "12") (pinfunction "8Q_12") (pintype "tri_state"))
      (node (ref "R48") (pin "1") (pinfunction "1_1") (pintype "passive"))
    )
    (net (code "72") (name "Net-(LED1-PadA)") (class "Default")
      (node (ref "LED1") (pin "A") (pinfunction "A_A") (pintype "passive"))
      (node (ref "U$1") (pin "D13") (pinfunction "D13_D13") (pintype "bidirectional"))
    )
    (net (code "73") (name "Net-(Q1-B)") (class "Default")
      (node (ref "Q1") (pin "1") (pinfunction "B_1") (pintype "passive"))
      (node (ref "R49") (pin "2") (pinfunction "2_2") (pintype "passive"))
    )
    (net (code "74") (name "Net-(Q1-C)") (class "Default")
      (node (ref "JP1") (pin "1") (pinfunction "1_1") (pintype "passive"))
      (node (ref "Q1") (pin "3") (pinfunction "C_3") (pintype "passive"))
      (node (ref "R53") (pin "2") (pinfunction "2_2") (pintype "passive"))
    )
    (net (code "75") (name "Net-(Q2-B)") (class "Default")
      (node (ref "Q2") (pin "1") (pinfunction "B_1") (pintype "passive"))
      (node (ref "R50") (pin "2") (pinfunction "2_2") (pintype "passive"))
    )
    (net (code "76") (name "Net-(Q2-C)") (class "Default")
      (node (ref "JP2") (pin "1") (pinfunction "1_1") (pintype "passive"))
      (node (ref "Q2") (pin "3") (pinfunction "C_3") (pintype "passive"))
      (node (ref "R54") (pin "2") (pinfunction "2_2") (pintype "passive"))
    )
    (net (code "77") (name "Net-(Q3-B)") (class "Default")
      (node (ref "Q3") (pin "1") (pinfunction "B_1") (pintype "passive"))
      (node (ref "R51") (pin "2") (pinfunction "2_2") (pintype "passive"))
    )
    (net (code "78") (name "Net-(Q3-C)") (class "Default")
      (node (ref "JP3") (pin "1") (pinfunction "1_1") (pintype "passive"))
      (node (ref "Q3") (pin "3") (pinfunction "C_3") (pintype "passive"))
      (node (ref "R55") (pin "2") (pinfunction "2_2") (pintype "passive"))
    )
    (net (code "79") (name "Net-(Q4-B)") (class "Default")
      (node (ref "Q4") (pin "1") (pinfunction "B_1") (pintype "passive"))
      (node (ref "R52") (pin "2") (pinfunction "2_2") (pintype "passive"))
    )
    (net (code "80") (name "Net-(Q4-C)") (class "Default")
      (node (ref "JP4") (pin "1") (pinfunction "1_1") (pintype "passive"))
      (node (ref "Q4") (pin "3") (pinfunction "C_3") (pintype "passive"))
      (node (ref "R56") (pin "2") (pinfunction "2_2") (pintype "passive"))
    )
    (net (code "81") (name "Net-(R1-Pad2)") (class "Default")
      (node (ref "R1") (pin "2") (pinfunction "2_2") (pintype "passive"))
      (node (ref "SV1") (pin "3") (pinfunction "3_3") (pintype "passive"))
    )
    (net (code "82") (name "Net-(R2-Pad2)") (class "Default")
      (node (ref "R2") (pin "2") (pinfunction "2_2") (pintype "passive"))
      (node (ref "SV2") (pin "3") (pinfunction "3_3") (pintype "passive"))
    )
    (net (code "83") (name "Net-(R3-Pad2)") (class "Default")
      (node (ref "R3") (pin "2") (pinfunction "2_2") (pintype "passive"))
      (node (ref "SV3") (pin "3") (pinfunction "3_3") (pintype "passive"))
    )
    (net (code "84") (name "Net-(R4-Pad2)") (class "Default")
      (node (ref "R4") (pin "2") (pinfunction "2_2") (pintype "passive"))
      (node (ref "SV4") (pin "3") (pinfunction "3_3") (pintype "passive"))
    )
    (net (code "85") (name "Net-(R5-Pad2)") (class "Default")
      (node (ref "R5") (pin "2") (pinfunction "2_2") (pintype "passive"))
      (node (ref "SV5") (pin "3") (pinfunction "3_3") (pintype "passive"))
    )
    (net (code "86") (name "Net-(R6-Pad2)") (class "Default")
      (node (ref "R6") (pin "2") (pinfunction "2_2") (pintype "passive"))
      (node (ref "SV6") (pin "3") (pinfunction "3_3") (pintype "passive"))
    )
    (net (code "87") (name "Net-(R7-Pad2)") (class "Default")
      (node (ref "R7") (pin "2") (pinfunction "2_2") (pintype "passive"))
      (node (ref "SV7") (pin "3") (pinfunction "3_3") (pintype "passive"))
    )
    (net (code "88") (name "Net-(R8-Pad2)") (class "Default")
      (node (ref "R8") (pin "2") (pinfunction "2_2") (pintype "passive"))
      (node (ref "SV8") (pin "3") (pinfunction "3_3") (pintype "passive"))
    )
    (net (code "89") (name "Net-(R9-Pad2)") (class "Default")
      (node (ref "R9") (pin "2") (pinfunction "2_2") (pintype "passive"))
      (node (ref "SV9") (pin "3") (pinfunction "3_3") (pintype "passive"))
    )
    (net (code "90") (name "Net-(R10-Pad2)") (class "Default")
      (node (ref "R10") (pin "2") (pinfunction "2_2") (pintype "passive"))
      (node (ref "SV10") (pin "3") (pinfunction "3_3") (pintype "passive"))
    )
    (net (code "91") (name "Net-(R11-Pad2)") (class "Default")
      (node (ref "R11") (pin "2") (pinfunction "2_2") (pintype "passive"))
      (node (ref "SV11") (pin "3") (pinfunction "3_3") (pintype "passive"))
    )
    (net (code "92") (name "Net-(R12-Pad2)") (class "Default")
      (node (ref "R12") (pin "2") (pinfunction "2_2") (pintype "passive"))
      (node (ref "SV12") (pin "3") (pinfunction "3_3") (pintype "passive"))
    )
    (net (code "93") (name "Net-(R13-Pad2)") (class "Default")
      (node (ref "R13") (pin "2") (pinfunction "2_2") (pintype "passive"))
      (node (ref "SV14") (pin "3") (pinfunction "3_3") (pintype "passive"))
    )
    (net (code "94") (name "Net-(R14-Pad2)") (class "Default")
      (node (ref "R14") (pin "2") (pinfunction "2_2") (pintype "passive"))
      (node (ref "SV13") (pin "3") (pinfunction "3_3") (pintype "passive"))
    )
    (net (code "95") (name "Net-(R15-Pad2)") (class "Default")
      (node (ref "R15") (pin "2") (pinfunction "2_2") (pintype "passive"))
      (node (ref "SV15") (pin "3") (pinfunction "3_3") (pintype "passive"))
    )
    (net (code "96") (name "Net-(R16-Pad2)") (class "Default")
      (node (ref "R16") (pin "2") (pinfunction "2_2") (pintype "passive"))
      (node (ref "SV16") (pin "3") (pinfunction "3_3") (pintype "passive"))
    )
    (net (code "97") (name "Net-(R17-Pad2)") (class "Default")
      (node (ref "R17") (pin "2") (pinfunction "2_2") (pintype "passive"))
      (node (ref "SV1") (pin "2") (pinfunction "2_2") (pintype "passive"))
    )
    (net (code "98") (name "Net-(R18-Pad2)") (class "Default")
      (node (ref "R18") (pin "2") (pinfunction "2_2") (pintype "passive"))
      (node (ref "SV2") (pin "2") (pinfunction "2_2") (pintype "passive"))
    )
    (net (code "99") (name "Net-(R19-Pad2)") (class "Default")
      (node (ref "R19") (pin "2") (pinfunction "2_2") (pintype "passive"))
      (node (ref "SV3") (pin "2") (pinfunction "2_2") (pintype "passive"))
    )
    (net (code "100") (name "Net-(R20-Pad2)") (class "Default")
      (node (ref "R20") (pin "2") (pinfunction "2_2") (pintype "passive"))
      (node (ref "SV4") (pin "2") (pinfunction "2_2") (pintype "passive"))
    )
    (net (code "101") (name "Net-(R21-Pad2)") (class "Default")
      (node (ref "R21") (pin "2") (pinfunction "2_2") (pintype "passive"))
      (node (ref "SV5") (pin "2") (pinfunction "2_2") (pintype "passive"))
    )
    (net (code "102") (name "Net-(R22-Pad2)") (class "Default")
      (node (ref "R22") (pin "2") (pinfunction "2_2") (pintype "passive"))
      (node (ref "SV6") (pin "2") (pinfunction "2_2") (pintype "passive"))
    )
    (net (code "103") (name "Net-(R23-Pad2)") (class "Default")
      (node (ref "R23") (pin "2") (pinfunction "2_2") (pintype "passive"))
      (node (ref "SV7") (pin "2") (pinfunction "2_2") (pintype "passive"))
    )
    (net (code "104") (name "Net-(R24-Pad2)") (class "Default")
      (node (ref "R24") (pin "2") (pinfunction "2_2") (pintype "passive"))
      (node (ref "SV8") (pin "2") (pinfunction "2_2") (pintype "passive"))
    )
    (net (code "105") (name "Net-(R25-Pad2)") (class "Default")
      (node (ref "R25") (pin "2") (pinfunction "2_2") (pintype "passive"))
      (node (ref "SV9") (pin "2") (pinfunction "2_2") (pintype "passive"))
    )
    (net (code "106") (name "Net-(R26-Pad2)") (class "Default")
      (node (ref "R26") (pin "2") (pinfunction "2_2") (pintype "passive"))
      (node (ref "SV10") (pin "2") (pinfunction "2_2") (pintype "passive"))
    )
    (net (code "107") (name "Net-(R27-Pad2)") (class "Default")
      (node (ref "R27") (pin "2") (pinfunction "2_2") (pintype "passive"))
      (node (ref "SV11") (pin "2") (pinfunction "2_2") (pintype "passive"))
    )
    (net (code "108") (name "Net-(R28-Pad2)") (class "Default")
      (node (ref "R28") (pin "2") (pinfunction "2_2") (pintype "passive"))
      (node (ref "SV12") (pin "2") (pinfunction "2_2") (pintype "passive"))
    )
    (net (code "109") (name "Net-(R29-Pad2)") (class "Default")
      (node (ref "R29") (pin "2") (pinfunction "2_2") (pintype "passive"))
      (node (ref "SV13") (pin "2") (pinfunction "2_2") (pintype "passive"))
    )
    (net (code "110") (name "Net-(R30-Pad2)") (class "Default")
      (node (ref "R30") (pin "2") (pinfunction "2_2") (pintype "passive"))
      (node (ref "SV14") (pin "2") (pinfunction "2_2") (pintype "passive"))
    )
    (net (code "111") (name "Net-(R31-Pad2)") (class "Default")
      (node (ref "R31") (pin "2") (pinfunction "2_2") (pintype "passive"))
      (node (ref "SV15") (pin "2") (pinfunction "2_2") (pintype "passive"))
    )
    (net (code "112") (name "Net-(R32-Pad2)") (class "Default")
      (node (ref "R32") (pin "2") (pinfunction "2_2") (pintype "passive"))
      (node (ref "SV16") (pin "2") (pinfunction "2_2") (pintype "passive"))
    )
    (net (code "113") (name "Net-(R33-Pad2)") (class "Default")
      (node (ref "R33") (pin "2") (pinfunction "2_2") (pintype "passive"))
      (node (ref "SV9") (pin "1") (pinfunction "1_1") (pintype "passive"))
    )
    (net (code "114") (name "Net-(R34-Pad2)") (class "Default")
      (node (ref "R34") (pin "2") (pinfunction "2_2") (pintype "passive"))
      (node (ref "SV10") (pin "1") (pinfunction "1_1") (pintype "passive"))
    )
    (net (code "115") (name "Net-(R35-Pad2)") (class "Default")
      (node (ref "R35") (pin "2") (pinfunction "2_2") (pintype "passive"))
      (node (ref "SV11") (pin "1") (pinfunction "1_1") (pintype "passive"))
    )
    (net (code "116") (name "Net-(R36-Pad2)") (class "Default")
      (node (ref "R36") (pin "2") (pinfunction "2_2") (pintype "passive"))
      (node (ref "SV12") (pin "1") (pinfunction "1_1") (pintype "passive"))
    )
    (net (code "117") (name "Net-(R37-Pad2)") (class "Default")
      (node (ref "R37") (pin "2") (pinfunction "2_2") (pintype "passive"))
      (node (ref "SV13") (pin "1") (pinfunction "1_1") (pintype "passive"))
    )
    (net (code "118") (name "Net-(R38-Pad2)") (class "Default")
      (node (ref "R38") (pin "2") (pinfunction "2_2") (pintype "passive"))
      (node (ref "SV14") (pin "1") (pinfunction "1_1") (pintype "passive"))
    )
    (net (code "119") (name "Net-(R39-Pad2)") (class "Default")
      (node (ref "R39") (pin "2") (pinfunction "2_2") (pintype "passive"))
      (node (ref "SV15") (pin "1") (pinfunction "1_1") (pintype "passive"))
    )
    (net (code "120") (name "Net-(R40-Pad2)") (class "Default")
      (node (ref "R40") (pin "2") (pinfunction "2_2") (pintype "passive"))
      (node (ref "SV16") (pin "1") (pinfunction "1_1") (pintype "passive"))
    )
    (net (code "121") (name "Net-(R41-Pad2)") (class "Default")
      (node (ref "R41") (pin "2") (pinfunction "2_2") (pintype "passive"))
      (node (ref "SV1") (pin "1") (pinfunction "1_1") (pintype "passive"))
    )
    (net (code "122") (name "Net-(R42-Pad2)") (class "Default")
      (node (ref "R42") (pin "2") (pinfunction "2_2") (pintype "passive"))
      (node (ref "SV2") (pin "1") (pinfunction "1_1") (pintype "passive"))
    )
    (net (code "123") (name "Net-(R43-Pad2)") (class "Default")
      (node (ref "R43") (pin "2") (pinfunction "2_2") (pintype "passive"))
      (node (ref "SV3") (pin "1") (pinfunction "1_1") (pintype "passive"))
    )
    (net (code "124") (name "Net-(R44-Pad2)") (class "Default")
      (node (ref "R44") (pin "2") (pinfunction "2_2") (pintype "passive"))
      (node (ref "SV4") (pin "1") (pinfunction "1_1") (pintype "passive"))
    )
    (net (code "125") (name "Net-(R45-Pad2)") (class "Default")
      (node (ref "R45") (pin "2") (pinfunction "2_2") (pintype "passive"))
      (node (ref "SV5") (pin "1") (pinfunction "1_1") (pintype "passive"))
    )
    (net (code "126") (name "Net-(R46-Pad2)") (class "Default")
      (node (ref "R46") (pin "2") (pinfunction "2_2") (pintype "passive"))
      (node (ref "SV6") (pin "1") (pinfunction "1_1") (pintype "passive"))
    )
    (net (code "127") (name "Net-(R47-Pad2)") (class "Default")
      (node (ref "R47") (pin "2") (pinfunction "2_2") (pintype "passive"))
      (node (ref "SV7") (pin "1") (pinfunction "1_1") (pintype "passive"))
    )
    (net (code "128") (name "Net-(R48-Pad2)") (class "Default")
      (node (ref "R48") (pin "2") (pinfunction "2_2") (pintype "passive"))
      (node (ref "SV8") (pin "1") (pinfunction "1_1") (pintype "passive"))
    )
    (net (code "129") (name "Net-(U$1-PadA5)") (class "Default")
      (node (ref "U$1") (pin "A5") (pinfunction "A5_A5") (pintype "bidirectional"))
      (node (ref "U$2") (pin "COM") (pinfunction "COM_COM") (pintype "bidirectional"))
    )
    (net (code "130") (name "VCC") (class "Default")
      (node (ref "C1") (pin "1") (pinfunction "1_1") (pintype "passive"))
      (node (ref "C2") (pin "1") (pinfunction "1_1") (pintype "passive"))
      (node (ref "C3") (pin "1") (pinfunction "1_1") (pintype "passive"))
      (node (ref "C4") (pin "1") (pinfunction "1_1") (pintype "passive"))
      (node (ref "C5") (pin "1") (pinfunction "1_1") (pintype "passive"))
      (node (ref "C6") (pin "1") (pinfunction "1_1") (pintype "passive"))
      (node (ref "C7") (pin "1") (pinfunction "1_1") (pintype "passive"))
      (node (ref "IC1") (pin "20") (pinfunction "VCC_20") (pintype "power_in"))
      (node (ref "IC2") (pin "20") (pinfunction "VCC_20") (pintype "power_in"))
      (node (ref "IC3") (pin "20") (pinfunction "VCC_20") (pintype "power_in"))
      (node (ref "IC4") (pin "20") (pinfunction "VCC_20") (pintype "power_in"))
      (node (ref "IC5") (pin "20") (pinfunction "VCC_20") (pintype "power_in"))
      (node (ref "IC6") (pin "20") (pinfunction "VCC_20") (pintype "power_in"))
      (node (ref "IC7") (pin "16") (pinfunction "VCC_16") (pintype "power_in"))
      (node (ref "IC7") (pin "6") (pinfunction "G1_6") (pintype "input"))
      (node (ref "R53") (pin "1") (pinfunction "1_1") (pintype "passive"))
      (node (ref "R54") (pin "1") (pinfunction "1_1") (pintype "passive"))
      (node (ref "R55") (pin "1") (pinfunction "1_1") (pintype "passive"))
      (node (ref "R56") (pin "1") (pinfunction "1_1") (pintype "passive"))
      (node (ref "U$1") (pin "5V") (pinfunction "5.5V_5V") (pintype "bidirectional"))
      (node (ref "U$2") (pin "L1") (pinfunction "L1_L1") (pintype "bidirectional"))
    )
    (net (code "131") (name "unconnected-(IC7A-Y6-Pad9)") (class "Default")
      (node (ref "IC7") (pin "9") (pinfunction "Y6_9") (pintype "output"))
    )
    (net (code "132") (name "unconnected-(IC7A-Y7-Pad7)") (class "Default")
      (node (ref "IC7") (pin "7") (pinfunction "Y7_7") (pintype "output"))
    )
    (net (code "133") (name "unconnected-(U$1-Pad3.3V)") (class "Default")
      (node (ref "U$1") (pin "3.3V") (pinfunction "3.3V_3.3V") (pintype "bidirectional"))
    )
    (net (code "134") (name "unconnected-(U$1-PadA6)") (class "Default")
      (node (ref "U$1") (pin "A6") (pinfunction "A6_A6") (pintype "bidirectional"))
    )
    (net (code "135") (name "unconnected-(U$1-PadA7)") (class "Default")
      (node (ref "U$1") (pin "A7") (pinfunction "A7_A7") (pintype "bidirectional"))
    )
    (net (code "136") (name "unconnected-(U$1-PadAREF)") (class "Default")
      (node (ref "U$1") (pin "AREF") (pinfunction "AREF_AREF") (pintype "bidirectional"))
    )
    (net (code "137") (name "unconnected-(U$1-PadICSP1)") (class "Default")
      (node (ref "U$1") (pin "ICSP1") (pinfunction "ICSP1_ICSP1") (pintype "bidirectional"))
    )
    (net (code "138") (name "unconnected-(U$1-PadICSP2)") (class "Default")
      (node (ref "U$1") (pin "ICSP2") (pinfunction "ICSP2_ICSP2") (pintype "bidirectional"))
    )
    (net (code "139") (name "unconnected-(U$1-PadICSP3)") (class "Default")
      (node (ref "U$1") (pin "ICSP3") (pinfunction "ICSP3_ICSP3") (pintype "bidirectional"))
    )
    (net (code "140") (name "unconnected-(U$1-PadICSP4)") (class "Default")
      (node (ref "U$1") (pin "ICSP4") (pinfunction "ICSP4_ICSP4") (pintype "bidirectional"))
    )
    (net (code "141") (name "unconnected-(U$1-PadICSP5)") (class "Default")
      (node (ref "U$1") (pin "ICSP5") (pinfunction "ICSP5_ICSP5") (pintype "bidirectional"))
    )
    (net (code "142") (name "unconnected-(U$1-PadICSP6)") (class "Default")
      (node (ref "U$1") (pin "ICSP6") (pinfunction "ICSP6_ICSP6") (pintype "bidirectional"))
    )
    (net (code "143") (name "unconnected-(U$1-PadRAW)") (class "Default")
      (node (ref "U$1") (pin "RAW") (pinfunction "RAW_RAW") (pintype "bidirectional"))
    )
    (net (code "144") (name "unconnected-(U$1-PadRST)") (class "Default")
      (node (ref "U$1") (pin "RST") (pinfunction "RST_RST") (pintype "bidirectional"))
    )
    (net (code "145") (name "unconnected-(U$1-PadRST1)") (class "Default")
      (node (ref "U$1") (pin "RST1") (pinfunction "RST1_RST1") (pintype "bidirectional"))
    )
    (net (code "146") (name "unconnected-(U$1-PadRX1)") (class "Default")
      (node (ref "U$1") (pin "RX1") (pinfunction "RX1_RX1") (pintype "bidirectional"))
    )
    (net (code "147") (name "unconnected-(U$1-PadTX0)") (class "Default")
      (node (ref "U$1") (pin "TX0") (pinfunction "TX0_TX0") (pintype "bidirectional"))
    )
  )
)
